# midiwall.net
KiCad netlist of a schematic drawn in EAGLE
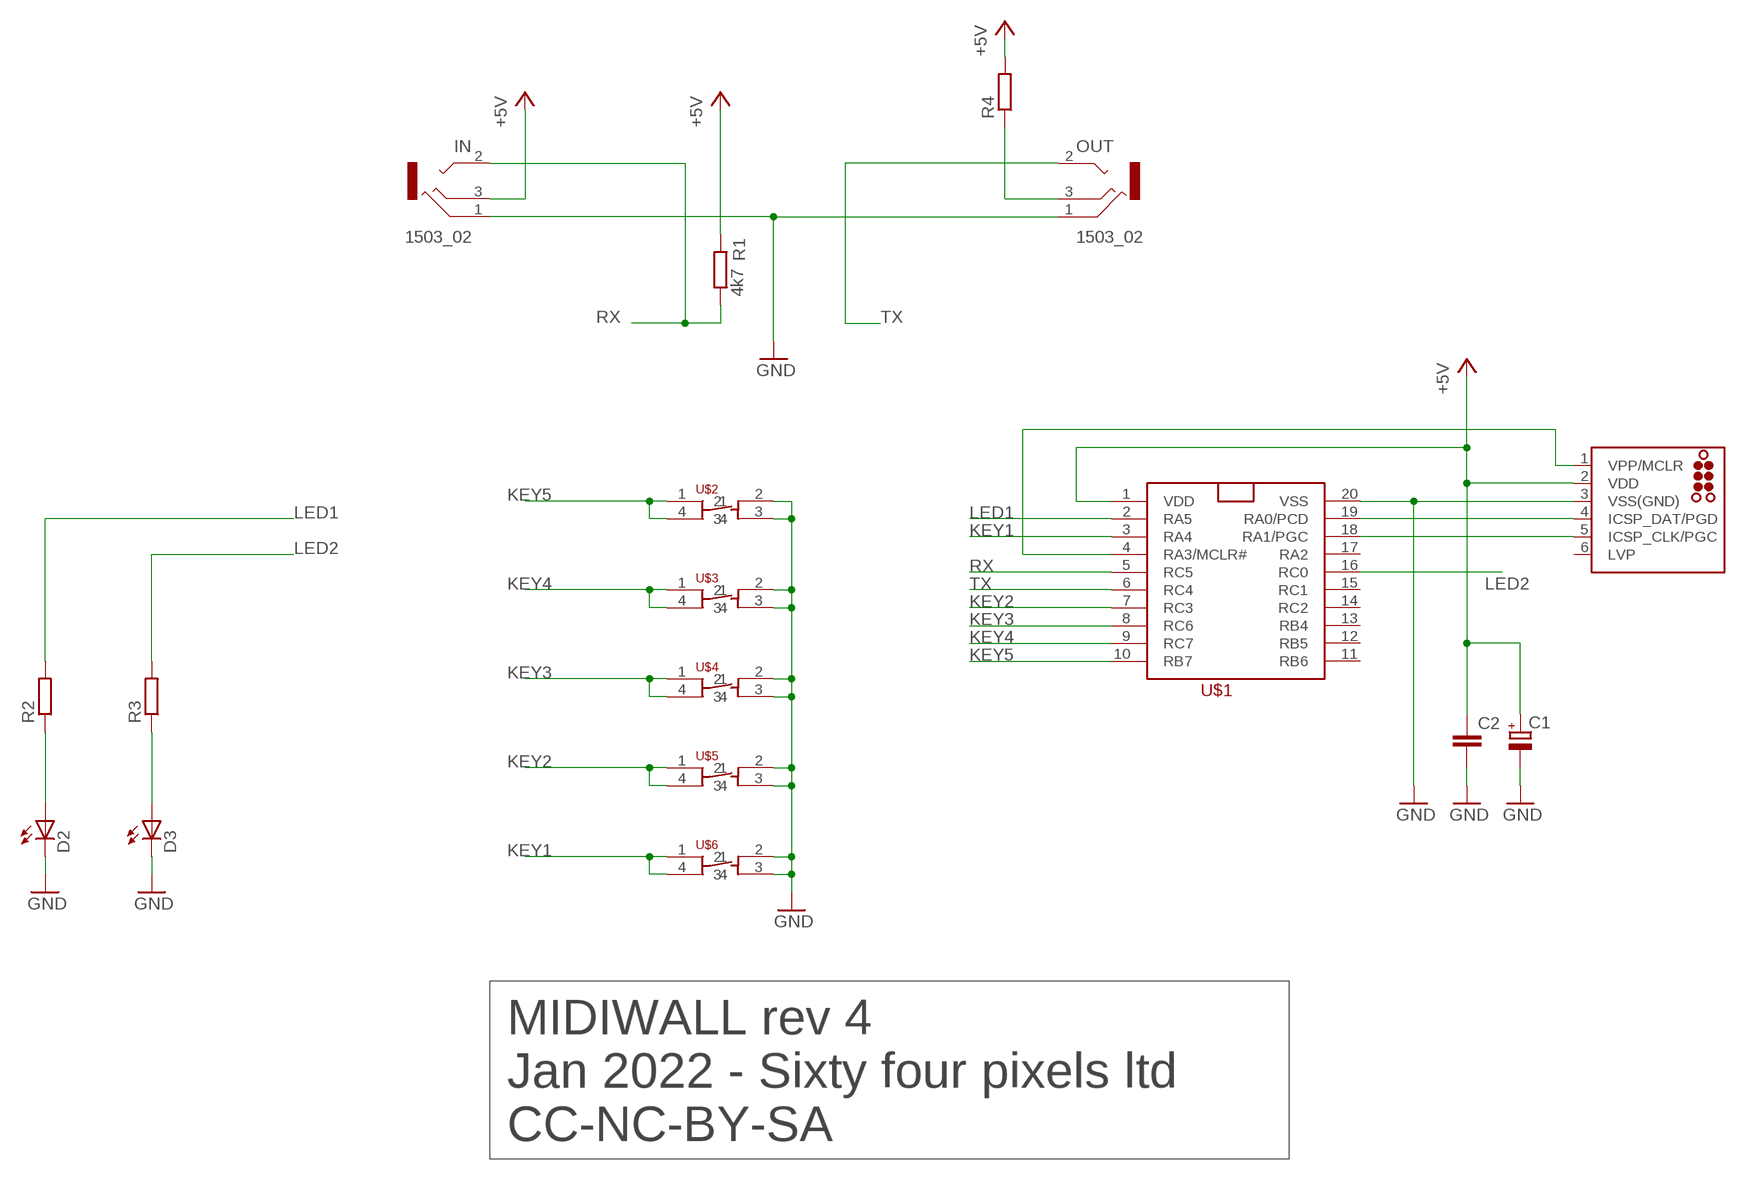
[diagram p0: schematic, sheet 1]

(export (version "E")
  (design (tool "Eeschema 10.0.6"))
  (components
    (comp (ref "C1")
      (value "CPOL-EUSMCB")
      (footprint "eagle-import:SMC_B")
      (libsource (lib "eagle-import") (part "CPOL-EUSMCB"))
    )
    (comp (ref "C2")
      (value "C-EUC0805")
      (footprint "eagle-import:C0805")
      (libsource (lib "eagle-import") (part "C-EUC0805"))
    )
    (comp (ref "D2")
      (value "LEDCHIPLED_0805")
      (footprint "eagle-import:CHIPLED_0805")
      (libsource (lib "eagle-import") (part "LEDCHIPLED_0805"))
    )
    (comp (ref "D3")
      (value "LEDCHIPLED_0805")
      (footprint "eagle-import:CHIPLED_0805")
      (libsource (lib "eagle-import") (part "LEDCHIPLED_0805"))
    )
    (comp (ref "ICSP")
      (value "TC2030-MCP-NL")
      (footprint "eagle-import:TC2030-MCP-NL")
      (libsource (lib "eagle-import") (part "TC2030-MCP-NL"))
    )
    (comp (ref "IN")
      (value "1503_02")
      (footprint "eagle-import:1503_02")
      (libsource (lib "eagle-import") (part "1503_02"))
    )
    (comp (ref "OUT")
      (value "1503_02")
      (footprint "eagle-import:1503_02")
      (libsource (lib "eagle-import") (part "1503_02"))
    )
    (comp (ref "R1")
      (value "4k7")
      (footprint "eagle-import:R0805")
      (libsource (lib "eagle-import") (part "R-EU_R0805"))
    )
    (comp (ref "R2")
      (value "R-EU_R0805")
      (footprint "eagle-import:R0805")
      (libsource (lib "eagle-import") (part "R-EU_R0805"))
    )
    (comp (ref "R3")
      (value "R-EU_R0805")
      (footprint "eagle-import:R0805")
      (libsource (lib "eagle-import") (part "R-EU_R0805"))
    )
    (comp (ref "R4")
      (value "R-EU_R0805")
      (footprint "eagle-import:R0805")
      (libsource (lib "eagle-import") (part "R-EU_R0805"))
    )
    (comp (ref "U$1")
      (value "PIC16F15345")
      (footprint "eagle-import:TSSOP20")
      (libsource (lib "eagle-import") (part "PIC16F15345"))
    )
    (comp (ref "U$2")
      (value "6MMTACTSMT")
      (footprint "eagle-import:6MMTACTSMT")
      (libsource (lib "eagle-import") (part "6MMTACTSMT"))
    )
    (comp (ref "U$3")
      (value "6MMTACTSMT")
      (footprint "eagle-import:6MMTACTSMT")
      (libsource (lib "eagle-import") (part "6MMTACTSMT"))
    )
    (comp (ref "U$4")
      (value "6MMTACTSMT")
      (footprint "eagle-import:6MMTACTSMT")
      (libsource (lib "eagle-import") (part "6MMTACTSMT"))
    )
    (comp (ref "U$5")
      (value "6MMTACTSMT")
      (footprint "eagle-import:6MMTACTSMT")
      (libsource (lib "eagle-import") (part "6MMTACTSMT"))
    )
    (comp (ref "U$6")
      (value "6MMTACTSMT")
      (footprint "eagle-import:6MMTACTSMT")
      (libsource (lib "eagle-import") (part "6MMTACTSMT"))
    )
  )
  (nets
    (net (code "1") (name "+5V") (class "Default")
      (node (ref "C1") (pin "+") (pinfunction "+_+") (pintype "passive"))
      (node (ref "C2") (pin "1") (pinfunction "1_1") (pintype "passive"))
      (node (ref "ICSP") (pin "2") (pinfunction "VDD_2") (pintype "power_in"))
      (node (ref "IN") (pin "3") (pinfunction "3_3") (pintype "passive"))
      (node (ref "R1") (pin "2") (pinfunction "2_2") (pintype "passive"))
      (node (ref "R4") (pin "2") (pinfunction "2_2") (pintype "passive"))
      (node (ref "U$1") (pin "1") (pinfunction "VDD_1") (pintype "bidirectional"))
    )
    (net (code "2") (name "/KEY1") (class "Default")
      (node (ref "U$1") (pin "3") (pinfunction "RA4_3") (pintype "bidirectional"))
      (node (ref "U$6") (pin "1") (pinfunction "1_1") (pintype "bidirectional"))
      (node (ref "U$6") (pin "4") (pinfunction "4_4") (pintype "bidirectional"))
    )
    (net (code "3") (name "/KEY2") (class "Default")
      (node (ref "U$1") (pin "7") (pinfunction "RC3_7") (pintype "bidirectional"))
      (node (ref "U$5") (pin "1") (pinfunction "1_1") (pintype "bidirectional"))
      (node (ref "U$5") (pin "4") (pinfunction "4_4") (pintype "bidirectional"))
    )
    (net (code "4") (name "/KEY3") (class "Default")
      (node (ref "U$1") (pin "8") (pinfunction "RC6_8") (pintype "bidirectional"))
      (node (ref "U$4") (pin "1") (pinfunction "1_1") (pintype "bidirectional"))
      (node (ref "U$4") (pin "4") (pinfunction "4_4") (pintype "bidirectional"))
    )
    (net (code "5") (name "/KEY4") (class "Default")
      (node (ref "U$1") (pin "9") (pinfunction "RC7_9") (pintype "bidirectional"))
      (node (ref "U$3") (pin "1") (pinfunction "1_1") (pintype "bidirectional"))
      (node (ref "U$3") (pin "4") (pinfunction "4_4") (pintype "bidirectional"))
    )
    (net (code "6") (name "/KEY5") (class "Default")
      (node (ref "U$1") (pin "10") (pinfunction "RB7_10") (pintype "bidirectional"))
      (node (ref "U$2") (pin "1") (pinfunction "1_1") (pintype "bidirectional"))
      (node (ref "U$2") (pin "4") (pinfunction "4_4") (pintype "bidirectional"))
    )
    (net (code "7") (name "/LED1") (class "Default")
      (node (ref "R2") (pin "2") (pinfunction "2_2") (pintype "passive"))
      (node (ref "U$1") (pin "2") (pinfunction "RA5_2") (pintype "bidirectional"))
    )
    (net (code "8") (name "/LED2") (class "Default")
      (node (ref "R3") (pin "2") (pinfunction "2_2") (pintype "passive"))
      (node (ref "U$1") (pin "16") (pinfunction "RC0_16") (pintype "bidirectional"))
    )
    (net (code "9") (name "/RX") (class "Default")
      (node (ref "IN") (pin "2") (pinfunction "2_2") (pintype "passive"))
      (node (ref "R1") (pin "1") (pinfunction "1_1") (pintype "passive"))
      (node (ref "U$1") (pin "5") (pinfunction "RC5_5") (pintype "bidirectional"))
    )
    (net (code "10") (name "/TX") (class "Default")
      (node (ref "OUT") (pin "2") (pinfunction "2_2") (pintype "passive"))
      (node (ref "U$1") (pin "6") (pinfunction "RC4_6") (pintype "bidirectional"))
    )
    (net (code "11") (name "GND") (class "Default")
      (node (ref "C1") (pin "-") (pinfunction "-_-") (pintype "passive"))
      (node (ref "C2") (pin "2") (pinfunction "2_2") (pintype "passive"))
      (node (ref "D2") (pin "C") (pinfunction "C_C") (pintype "passive"))
      (node (ref "D3") (pin "C") (pinfunction "C_C") (pintype "passive"))
      (node (ref "ICSP") (pin "3") (pinfunction "VSS(GND)_3") (pintype "power_in"))
      (node (ref "IN") (pin "1") (pinfunction "1_1") (pintype "passive"))
      (node (ref "OUT") (pin "1") (pinfunction "1_1") (pintype "passive"))
      (node (ref "U$1") (pin "20") (pinfunction "VSS_20") (pintype "bidirectional"))
      (node (ref "U$2") (pin "2") (pinfunction "2_2") (pintype "bidirectional"))
      (node (ref "U$2") (pin "3") (pinfunction "3_3") (pintype "bidirectional"))
      (node (ref "U$3") (pin "2") (pinfunction "2_2") (pintype "bidirectional"))
      (node (ref "U$3") (pin "3") (pinfunction "3_3") (pintype "bidirectional"))
      (node (ref "U$4") (pin "2") (pinfunction "2_2") (pintype "bidirectional"))
      (node (ref "U$4") (pin "3") (pinfunction "3_3") (pintype "bidirectional"))
      (node (ref "U$5") (pin "2") (pinfunction "2_2") (pintype "bidirectional"))
      (node (ref "U$5") (pin "3") (pinfunction "3_3") (pintype "bidirectional"))
      (node (ref "U$6") (pin "2") (pinfunction "2_2") (pintype "bidirectional"))
      (node (ref "U$6") (pin "3") (pinfunction "3_3") (pintype "bidirectional"))
    )
    (net (code "12") (name "Net-(D2-PadA)") (class "Default")
      (node (ref "D2") (pin "A") (pinfunction "A_A") (pintype "passive"))
      (node (ref "R2") (pin "1") (pinfunction "1_1") (pintype "passive"))
    )
    (net (code "13") (name "Net-(D3-PadA)") (class "Default")
      (node (ref "D3") (pin "A") (pinfunction "A_A") (pintype "passive"))
      (node (ref "R3") (pin "1") (pinfunction "1_1") (pintype "passive"))
    )
    (net (code "14") (name "Net-(ICSP-ICSP_CLK{slash}PGC)") (class "Default")
      (node (ref "ICSP") (pin "5") (pinfunction "ICSP_CLK/PGC_5") (pintype "output"))
      (node (ref "U$1") (pin "18") (pinfunction "RA1/PGC_18") (pintype "bidirectional"))
    )
    (net (code "15") (name "Net-(ICSP-ICSP_DAT{slash}PGD)") (class "Default")
      (node (ref "ICSP") (pin "4") (pinfunction "ICSP_DAT/PGD_4") (pintype "bidirectional"))
      (node (ref "U$1") (pin "19") (pinfunction "RA0/PCD_19") (pintype "bidirectional"))
    )
    (net (code "16") (name "Net-(ICSP-VPP{slash}MCLR)") (class "Default")
      (node (ref "ICSP") (pin "1") (pinfunction "VPP/MCLR_1") (pintype "passive"))
      (node (ref "U$1") (pin "4") (pinfunction "RA3/MCLR#_4") (pintype "bidirectional"))
    )
    (net (code "17") (name "Net-(OUT-Pad3)") (class "Default")
      (node (ref "OUT") (pin "3") (pinfunction "3_3") (pintype "passive"))
      (node (ref "R4") (pin "1") (pinfunction "1_1") (pintype "passive"))
    )
    (net (code "18") (name "unconnected-(ICSP-LVP-Pad6)") (class "Default")
      (node (ref "ICSP") (pin "6") (pinfunction "LVP_6") (pintype "bidirectional"))
    )
    (net (code "19") (name "unconnected-(IN-2-Pad2@2)") (class "Default")
      (node (ref "IN") (pin "2@2") (pinfunction "2_2@2") (pintype "passive"))
    )
    (net (code "20") (name "unconnected-(OUT-2-Pad2@2)") (class "Default")
      (node (ref "OUT") (pin "2@2") (pinfunction "2_2@2") (pintype "passive"))
    )
    (net (code "21") (name "unconnected-(U$1-RA2-Pad17)") (class "Default")
      (node (ref "U$1") (pin "17") (pinfunction "RA2_17") (pintype "bidirectional"))
    )
    (net (code "22") (name "unconnected-(U$1-RB4-Pad13)") (class "Default")
      (node (ref "U$1") (pin "13") (pinfunction "RB4_13") (pintype "bidirectional"))
    )
    (net (code "23") (name "unconnected-(U$1-RB5-Pad12)") (class "Default")
      (node (ref "U$1") (pin "12") (pinfunction "RB5_12") (pintype "bidirectional"))
    )
    (net (code "24") (name "unconnected-(U$1-RB6-Pad11)") (class "Default")
      (node (ref "U$1") (pin "11") (pinfunction "RB6_11") (pintype "bidirectional"))
    )
    (net (code "25") (name "unconnected-(U$1-RC1-Pad15)") (class "Default")
      (node (ref "U$1") (pin "15") (pinfunction "RC1_15") (pintype "bidirectional"))
    )
    (net (code "26") (name "unconnected-(U$1-RC2-Pad14)") (class "Default")
      (node (ref "U$1") (pin "14") (pinfunction "RC2_14") (pintype "bidirectional"))
    )
  )
)
